# Inputs.net
KiCad netlist of a schematic drawn in Altium Designer
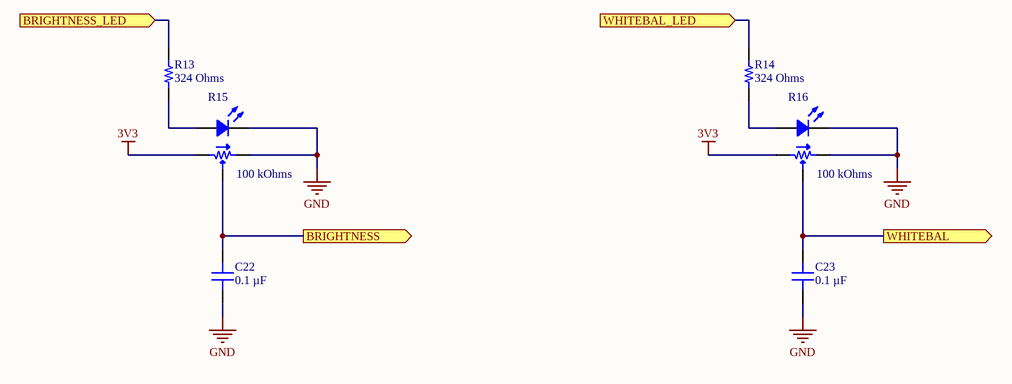
[diagram p0: Inputs.SchDoc]

(export (version "E")
  (design (tool "Eeschema 10.0.6"))
  (components
    (comp (ref "C22")
      (value "0.1 µF")
      (footprint "CAP 0603_1608")
      (description "CAP CER 0.1UF 10V X7R 0603")
      (fields (field (name "PART NUMBER") "CC0603KRX7R6BB104") (field (name "MANUFACTURER") "Yageo"))
      (libsource (lib "altiumlibrary.com") (part "Capacitor"))
    )
    (comp (ref "C23")
      (value "0.1 µF")
      (footprint "CAP 0603_1608")
      (description "CAP CER 0.1UF 10V X7R 0603")
      (fields (field (name "PART NUMBER") "CC0603KRX7R6BB104") (field (name "MANUFACTURER") "Yageo"))
      (libsource (lib "altiumlibrary.com") (part "Capacitor"))
    )
    (comp (ref "R13")
      (value "324 Ohms")
      (footprint "RES 0603_1608")
      (description "RES SMD 324 OHM 1% 1/10W 0603")
      (fields
        (field (name "PART NUMBER") "ERJ-3EKF3240V")
        (field (name "MANUFACTURER") "Panasonic Electronic Components")
      )
      (libsource (lib "altiumlibrary.com") (part "Resistor"))
    )
    (comp (ref "R14")
      (value "324 Ohms")
      (footprint "RES 0603_1608")
      (description "RES SMD 324 OHM 1% 1/10W 0603")
      (fields
        (field (name "PART NUMBER") "ERJ-3EKF3240V")
        (field (name "MANUFACTURER") "Panasonic Electronic Components")
      )
      (libsource (lib "altiumlibrary.com") (part "Resistor"))
    )
    (comp (ref "R15")
      (value "PTL45-15O0-104B1")
      (footprint "POT BOURNS PTL45-15xx")
      (description "SLIDE POT 100K OHM 0.125W TOP")
      (fields
        (field (name "RESISTANCE") "100 kOhms")
        (field (name "MANUFACTURER") "Bourns Inc.")
        (field (name "TOLERANCE") "±20%")
      )
      (libsource (lib "altiumlibrary.com") (part "POTENTIOMETER wLED"))
    )
    (comp (ref "R16")
      (value "PTL45-15O0-104B1")
      (footprint "POT BOURNS PTL45-15xx")
      (description "SLIDE POT 100K OHM 0.125W TOP")
      (fields
        (field (name "RESISTANCE") "100 kOhms")
        (field (name "MANUFACTURER") "Bourns Inc.")
        (field (name "TOLERANCE") "±20%")
      )
      (libsource (lib "altiumlibrary.com") (part "POTENTIOMETER wLED"))
    )
  )
  (nets
    (net (code "1") (name "/BRIGHTNESS") (class "Default")
      (node (ref "C22") (pin "2") (pinfunction "2_2") (pintype "passive"))
      (node (ref "R15") (pin "2") (pinfunction "2_2") (pintype "passive"))
    )
    (net (code "2") (name "/BRIGHTNESS_LED") (class "Default")
      (node (ref "R13") (pin "2") (pinfunction "2_2") (pintype "passive"))
    )
    (net (code "3") (name "/WHITEBAL") (class "Default")
      (node (ref "C23") (pin "2") (pinfunction "2_2") (pintype "passive"))
      (node (ref "R16") (pin "2") (pinfunction "2_2") (pintype "passive"))
    )
    (net (code "4") (name "/WHITEBAL_LED") (class "Default")
      (node (ref "R14") (pin "2") (pinfunction "2_2") (pintype "passive"))
    )
    (net (code "5") (name "3V3") (class "Default")
      (node (ref "R15") (pin "1") (pinfunction "1_1") (pintype "passive"))
      (node (ref "R16") (pin "1") (pinfunction "1_1") (pintype "passive"))
    )
    (net (code "6") (name "GND") (class "Default")
      (node (ref "C22") (pin "1") (pinfunction "1_1") (pintype "passive"))
      (node (ref "C23") (pin "1") (pinfunction "1_1") (pintype "passive"))
      (node (ref "R15") (pin "3") (pinfunction "3_3") (pintype "passive"))
      (node (ref "R15") (pin "E") (pinfunction "E_E") (pintype "passive"))
      (node (ref "R16") (pin "3") (pinfunction "3_3") (pintype "passive"))
      (node (ref "R16") (pin "E") (pinfunction "E_E") (pintype "passive"))
    )
    (net (code "7") (name "Net-(R13-Pad1)") (class "Default")
      (node (ref "R13") (pin "1") (pinfunction "1_1") (pintype "passive"))
      (node (ref "R15") (pin "B") (pinfunction "B_B") (pintype "passive"))
    )
    (net (code "8") (name "Net-(R14-Pad1)") (class "Default")
      (node (ref "R14") (pin "1") (pinfunction "1_1") (pintype "passive"))
      (node (ref "R16") (pin "B") (pinfunction "B_B") (pintype "passive"))
    )
  )
)
